# Payload.net
KiCad netlist of a schematic drawn in Altium Designer
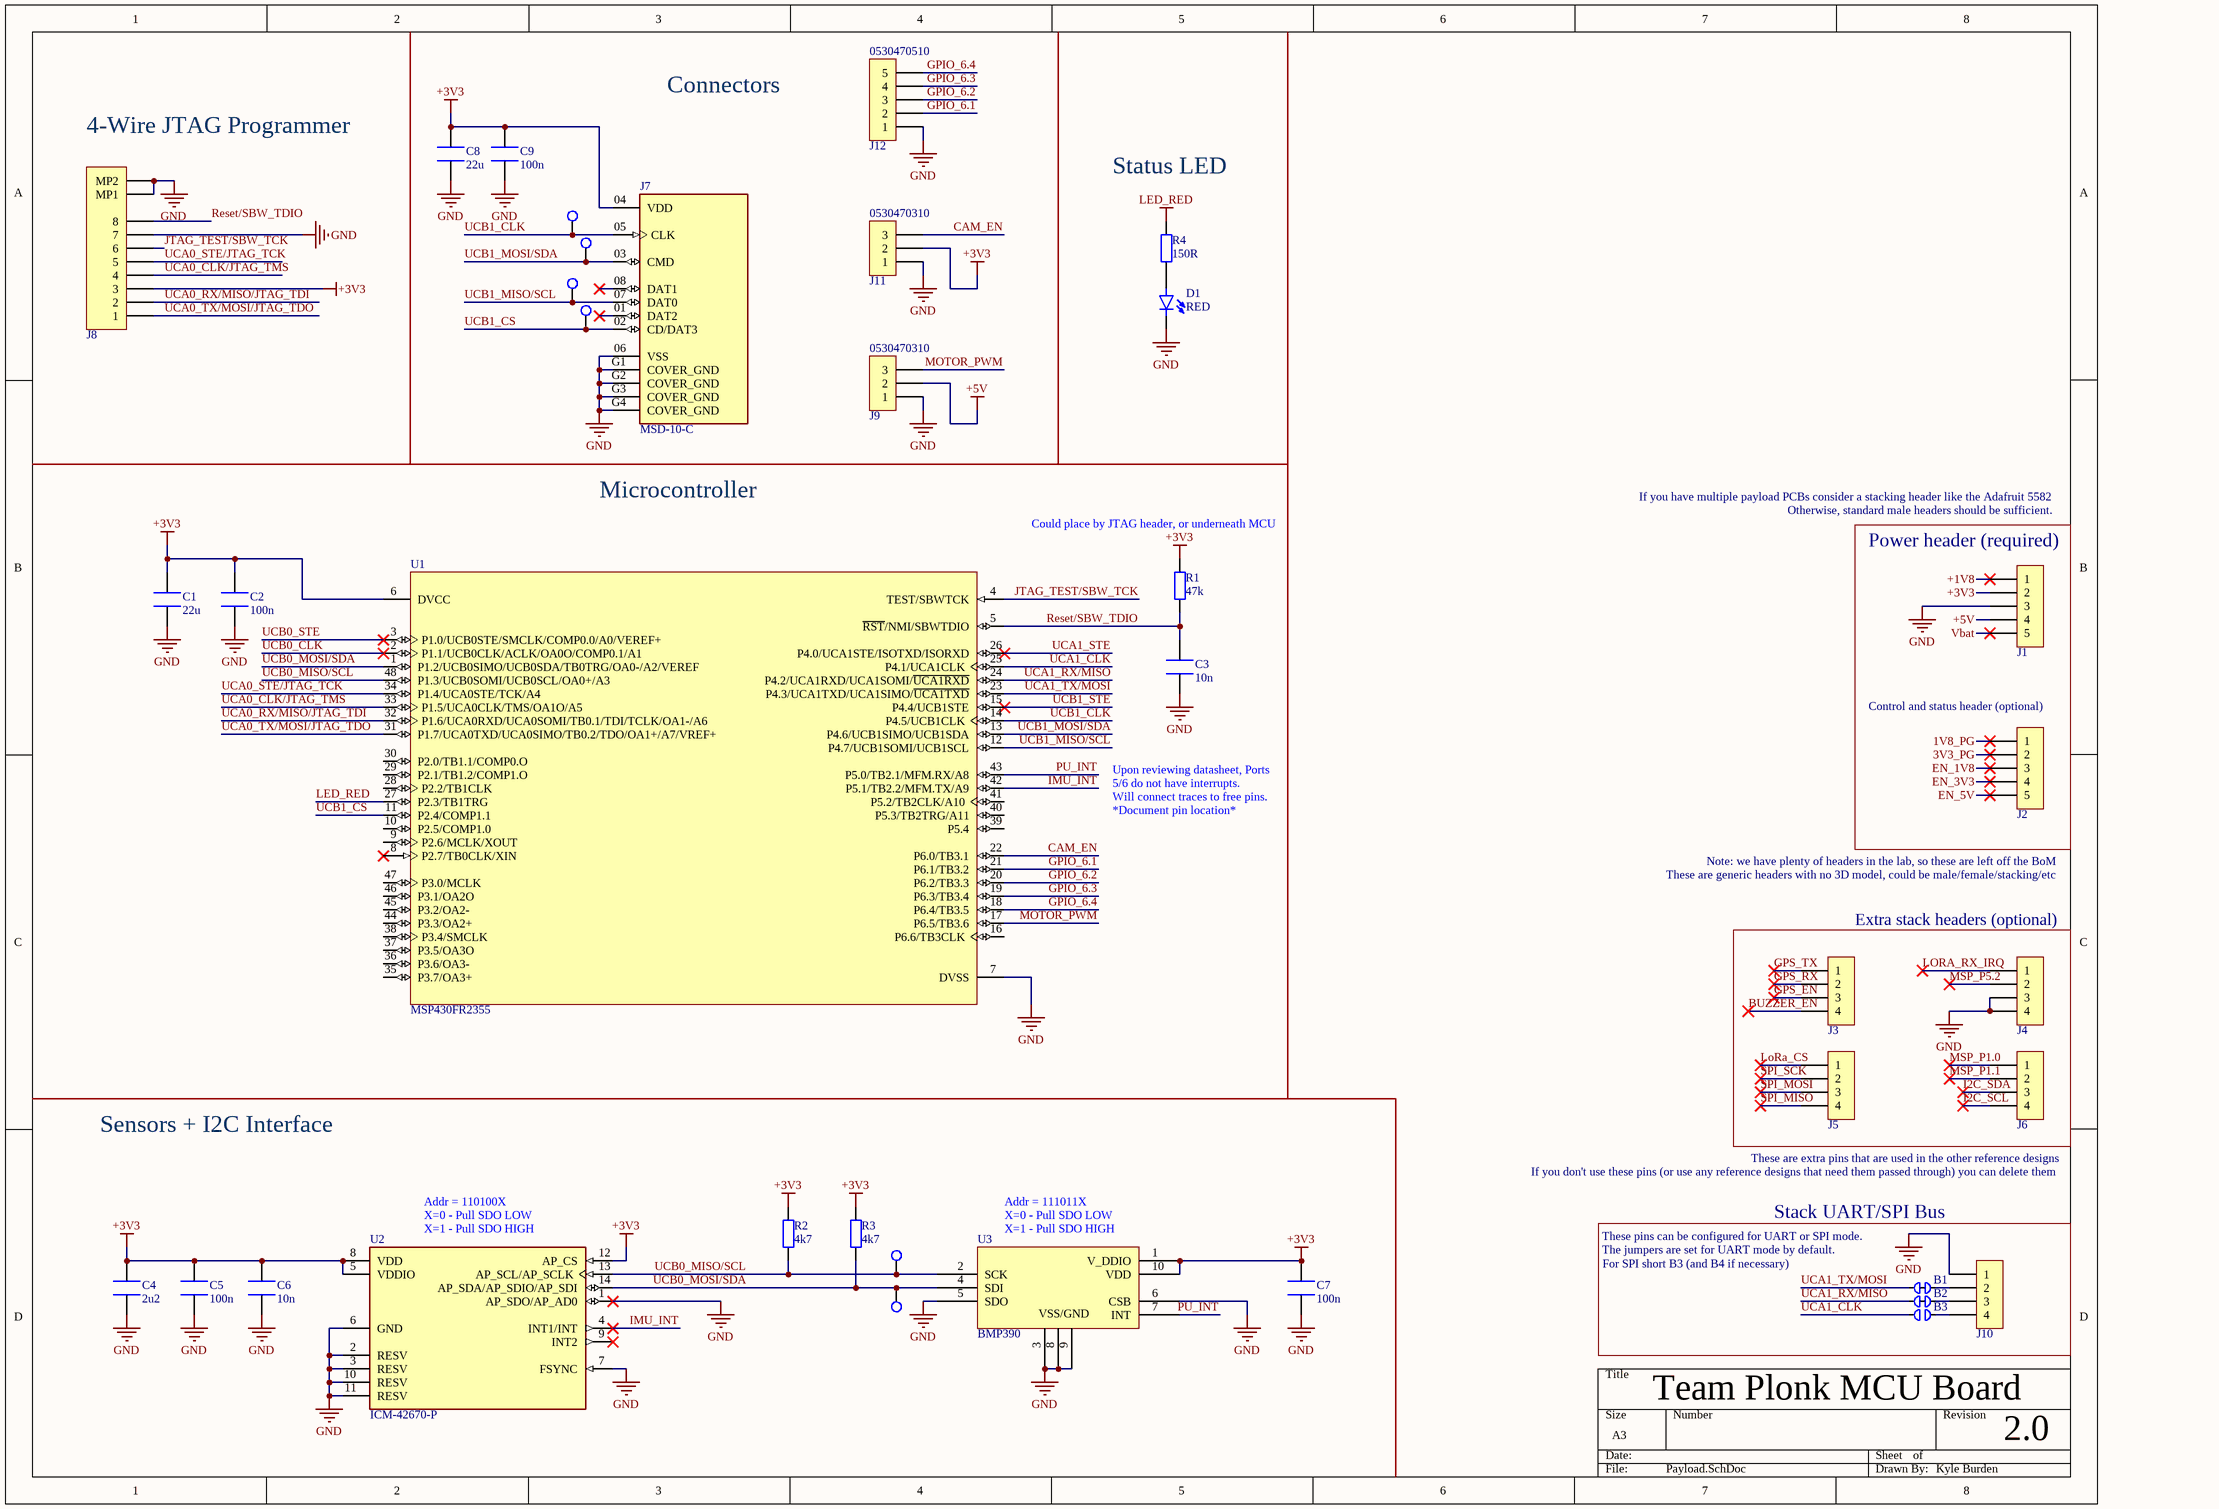
[diagram p0: Payload.SchDoc]

(export (version "E")
  (design (tool "Eeschema 10.0.6"))
  (components
    (comp (ref "B1")
      (value "Solder Jumper Normally Closed")
      (footprint "APSS Generic Components:Solder Bridge Chevron 0402 Closed")
      (libsource (lib "APSS Generic Components") (part "Solder Jumper Normally Closed"))
    )
    (comp (ref "B2")
      (value "Solder Jumper Normally Closed")
      (footprint "APSS Generic Components:Solder Bridge Chevron 0402 Closed")
      (libsource (lib "APSS Generic Components") (part "Solder Jumper Normally Closed"))
    )
    (comp (ref "B3")
      (value "Solder Jumper Normally Open")
      (footprint "APSS Generic Components:Solder Bridge Chevron 0402 Open")
      (libsource (lib "APSS Generic Components") (part "Solder Jumper Normally Open"))
    )
    (comp (ref "C1")
      (value "22u")
      (footprint "CAPACITOR_0805_2012M-70N")
      (description "Passive - Capacitor, Generic")
      (fields (field (name "TOLERANCE") "?%"))
      (libsource (lib "APSS Generic Components") (part "Generic Capacitor"))
    )
    (comp (ref "C2")
      (value "100n")
      (footprint "CAPACITOR_0805_2012M-70N")
      (description "Passive - Capacitor, Generic")
      (fields (field (name "TOLERANCE") "?%"))
      (libsource (lib "APSS Generic Components") (part "Generic Capacitor"))
    )
    (comp (ref "C3")
      (value "10n")
      (footprint "CAPACITOR_0805_2012M-70N")
      (description "Passive - Capacitor, Generic")
      (fields (field (name "TOLERANCE") "?%"))
      (libsource (lib "APSS Generic Components") (part "Generic Capacitor"))
    )
    (comp (ref "C4")
      (value "2u2")
      (footprint "CAPACITOR_0805_2012M-70N")
      (description "Passive - Capacitor, Generic")
      (fields (field (name "TOLERANCE") "?%"))
      (libsource (lib "APSS Generic Components") (part "Generic Capacitor"))
    )
    (comp (ref "C5")
      (value "100n")
      (footprint "CAPACITOR_0805_2012M-70N")
      (description "Passive - Capacitor, Generic")
      (fields (field (name "TOLERANCE") "?%"))
      (libsource (lib "APSS Generic Components") (part "Generic Capacitor"))
    )
    (comp (ref "C6")
      (value "10n")
      (footprint "CAPACITOR_0805_2012M-70N")
      (description "Passive - Capacitor, Generic")
      (fields (field (name "TOLERANCE") "?%"))
      (libsource (lib "APSS Generic Components") (part "Generic Capacitor"))
    )
    (comp (ref "C7")
      (value "100n")
      (footprint "CAPACITOR_0805_2012M-70N")
      (description "Passive - Capacitor, Generic")
      (fields (field (name "TOLERANCE") "?%"))
      (libsource (lib "APSS Generic Components") (part "Generic Capacitor"))
    )
    (comp (ref "C8")
      (value "22u")
      (footprint "CAPACITOR_0805_2012M-70N")
      (description "Passive - Capacitor, Generic")
      (fields (field (name "TOLERANCE") "?%"))
      (libsource (lib "APSS Generic Components") (part "Generic Capacitor"))
    )
    (comp (ref "C9")
      (value "100n")
      (footprint "CAPACITOR_0805_2012M-70N")
      (description "Passive - Capacitor, Generic")
      (fields (field (name "TOLERANCE") "?%"))
      (libsource (lib "APSS Generic Components") (part "Generic Capacitor"))
    )
    (comp (ref "D1")
      (value "LTST-C190 Series")
      (footprint "LED_0603_1608M_0.80mm")
      (description "Diode - LED, 0603")
      (fields (field (name "APSS STANDARD PART") "APSS Standard") (field (name "COLOUR") "RED"))
      (libsource (lib "PSAT_Library") (part "LTST-C190 Series"))
    )
    (comp (ref "J1")
      (value "Header - 2.54mm,1x5-pin")
      (footprint "HEADER_2.54MM_1x5PIN")
      (libsource (lib "APSS Generic Components") (part "Header - 2.54mm,1x5-pin"))
    )
    (comp (ref "J2")
      (value "Header - 2.54mm,1x5-pin")
      (footprint "HEADER_2.54MM_1x5PIN")
      (libsource (lib "APSS Generic Components") (part "Header - 2.54mm,1x5-pin"))
    )
    (comp (ref "J3")
      (value "Header - 2.54mm,1x4-pin")
      (footprint "HEADER_2.54MM_1x4PIN")
      (libsource (lib "APSS Generic Components") (part "Header - 2.54mm,1x4-pin"))
    )
    (comp (ref "J4")
      (value "Header - 2.54mm,1x4-pin")
      (footprint "HEADER_2.54MM_1x4PIN")
      (libsource (lib "APSS Generic Components") (part "Header - 2.54mm,1x4-pin"))
    )
    (comp (ref "J5")
      (value "Header - 2.54mm,1x4-pin")
      (footprint "HEADER_2.54MM_1x4PIN")
      (libsource (lib "APSS Generic Components") (part "Header - 2.54mm,1x4-pin"))
    )
    (comp (ref "J6")
      (value "Header - 2.54mm,1x4-pin")
      (footprint "HEADER_2.54MM_1x4PIN")
      (libsource (lib "APSS Generic Components") (part "Header - 2.54mm,1x4-pin"))
    )
    (comp (ref "J7")
      (value "MSD-10-C")
      (footprint "MSD-10-C")
      (description "SM Micro SD Card Connector")
      (libsource (lib "PSAT_Library") (part "MSD-10-C"))
    )
    (comp (ref "J8")
      (value "0532610871")
      (footprint "APSS Connectors:MOLEX_0532610871")
      (description "Connector - Picoblade 08-pin, SMT, RA")
      (fields (field (name "APSS STANDARD PART") "APSS Standard"))
      (libsource (lib "APSS Connectors") (part "0532610871"))
    )
    (comp (ref "J9")
      (value "0530470310")
      (footprint "APSS Connectors:MOLEX_0530470310")
      (description "Connector - Picoblade 03-pin, TH, STR")
      (fields (field (name "APSS STANDARD PART") "APSS Standard"))
      (libsource (lib "APSS Connectors") (part "0530470310"))
    )
    (comp (ref "J10")
      (value "HDR,2.54mm,1x4")
      (footprint "APSS Connectors:HEADER_2.54MM_1x4PIN")
      (description "Connector - 2.54mm, 1x4-pin")
      (libsource (lib "APSS Connectors") (part "HDR,2.54mm,1x4"))
    )
    (comp (ref "J11")
      (value "0530470310")
      (footprint "APSS Connectors:MOLEX_0530470310")
      (description "Connector - Picoblade 03-pin, TH, STR")
      (fields (field (name "APSS STANDARD PART") "APSS Standard"))
      (libsource (lib "APSS Connectors") (part "0530470310"))
    )
    (comp (ref "J12")
      (value "0530470510")
      (footprint "APSS Connectors:MOLEX_0530470510")
      (description "Connector - Picoblade 05-pin, TH, STR")
      (fields (field (name "APSS STANDARD PART") "APSS Standard"))
      (libsource (lib "APSS Connectors") (part "0530470510"))
    )
    (comp (ref "R1")
      (value "47k")
      (footprint "RESISTOR_0805_2012M-50N")
      (description "Passive - Resistor, Generic")
      (fields (field (name "TOLERANCE") "?%"))
      (libsource (lib "APSS Generic Components") (part "Generic Resistor"))
    )
    (comp (ref "R2")
      (value "4k7")
      (footprint "RESISTOR_0805_2012M-50N")
      (description "Passive - Resistor, Generic")
      (fields (field (name "TOLERANCE") "?%"))
      (libsource (lib "APSS Generic Components") (part "Generic Resistor"))
    )
    (comp (ref "R3")
      (value "4k7")
      (footprint "RESISTOR_0805_2012M-50N")
      (description "Passive - Resistor, Generic")
      (fields (field (name "TOLERANCE") "?%"))
      (libsource (lib "APSS Generic Components") (part "Generic Resistor"))
    )
    (comp (ref "R4")
      (value "150R")
      (footprint "Resistor_0805_2012M-50N")
      (description "0805 Surface Mount Resistor")
      (libsource (lib "PSAT_Library") (part "RES SM 0805"))
    )
    (comp (ref "TP1")
      (value "Test Point")
      (footprint "APSS Generic Components:Test Point Pad Medium")
      (libsource (lib "APSS Generic Components") (part "Test Point"))
    )
    (comp (ref "TP2")
      (value "Test Point")
      (footprint "APSS Generic Components:Test Point Pad Medium")
      (libsource (lib "APSS Generic Components") (part "Test Point"))
    )
    (comp (ref "TP3")
      (value "Test Point")
      (footprint "APSS Generic Components:Test Point Pad Medium")
      (libsource (lib "APSS Generic Components") (part "Test Point"))
    )
    (comp (ref "TP4")
      (value "Test Point")
      (footprint "APSS Generic Components:Test Point Pad Medium")
      (libsource (lib "APSS Generic Components") (part "Test Point"))
    )
    (comp (ref "TP5")
      (value "Test Point")
      (footprint "APSS Generic Components:Test Point Pad Medium")
      (libsource (lib "APSS Generic Components") (part "Test Point"))
    )
    (comp (ref "TP6")
      (value "Test Point")
      (footprint "APSS Generic Components:Test Point Pad Medium")
      (libsource (lib "APSS Generic Components") (part "Test Point"))
    )
    (comp (ref "U1")
      (value "MSP430FR2355")
      (footprint "PT0048A_N")
      (libsource (lib "PSAT_Library") (part "MSP430FR2355"))
    )
    (comp (ref "U2")
      (value "ICM-42670-P")
      (footprint "XDCR_ICM-42670-P-EXTENDED_PADS")
      (fields (field (name "APSS STANDARD PART") "APSS Standard"))
      (libsource (lib "PSAT_Library") (part "ICM-42670-P"))
    )
    (comp (ref "U3")
      (value "BMP390")
      (footprint "PSAT_Library:BMP390")
      (description "Pressure Sensor")
      (libsource (lib "PSAT_Library") (part "BMP390"))
    )
  )
  (nets
    (net (code "1") (name "+3V3") (class "Default")
      (node (ref "C1") (pin "2") (pinfunction "2_2") (pintype "passive"))
      (node (ref "C2") (pin "2") (pinfunction "2_2") (pintype "passive"))
      (node (ref "C4") (pin "2") (pinfunction "2_2") (pintype "passive"))
      (node (ref "C5") (pin "2") (pinfunction "2_2") (pintype "passive"))
      (node (ref "C6") (pin "2") (pinfunction "2_2") (pintype "passive"))
      (node (ref "C7") (pin "2") (pinfunction "2_2") (pintype "passive"))
      (node (ref "C8") (pin "2") (pinfunction "2_2") (pintype "passive"))
      (node (ref "C9") (pin "2") (pinfunction "2_2") (pintype "passive"))
      (node (ref "J1") (pin "2") (pinfunction "2_2") (pintype "passive"))
      (node (ref "J11") (pin "2") (pinfunction "2_2") (pintype "passive"))
      (node (ref "J7") (pin "04") (pinfunction "VDD_04") (pintype "power_in"))
      (node (ref "J8") (pin "3") (pinfunction "3_3") (pintype "passive"))
      (node (ref "R1") (pin "2") (pinfunction "2_2") (pintype "passive"))
      (node (ref "R2") (pin "2") (pinfunction "2_2") (pintype "passive"))
      (node (ref "R3") (pin "2") (pinfunction "2_2") (pintype "passive"))
      (node (ref "U1") (pin "6") (pinfunction "DVCC_6") (pintype "power_in"))
      (node (ref "U2") (pin "12") (pinfunction "AP_CS_12") (pintype "input"))
      (node (ref "U2") (pin "5") (pinfunction "VDDIO_5") (pintype "power_in"))
      (node (ref "U2") (pin "8") (pinfunction "VDD_8") (pintype "power_in"))
      (node (ref "U3") (pin "1") (pinfunction "V_DDIO_1") (pintype "passive"))
      (node (ref "U3") (pin "10") (pinfunction "VDD_10") (pintype "passive"))
    )
    (net (code "2") (name "+5V") (class "Default")
      (node (ref "J1") (pin "4") (pinfunction "4_4") (pintype "passive"))
      (node (ref "J9") (pin "2") (pinfunction "2_2") (pintype "passive"))
    )
    (net (code "3") (name "/+1V8") (class "Default")
      (node (ref "J1") (pin "1") (pinfunction "1_1") (pintype "passive+no_connect"))
    )
    (net (code "4") (name "/1V8_PG") (class "Default")
      (node (ref "J2") (pin "1") (pinfunction "1_1") (pintype "passive+no_connect"))
    )
    (net (code "5") (name "/3V3_PG") (class "Default")
      (node (ref "J2") (pin "2") (pinfunction "2_2") (pintype "passive+no_connect"))
    )
    (net (code "6") (name "/BUZZER_EN") (class "Default")
      (node (ref "J3") (pin "4") (pinfunction "4_4") (pintype "passive+no_connect"))
    )
    (net (code "7") (name "/CAM_EN") (class "Default")
      (node (ref "J11") (pin "3") (pinfunction "3_3") (pintype "passive"))
      (node (ref "U1") (pin "22") (pinfunction "P6.0/TB3.1_22") (pintype "bidirectional"))
    )
    (net (code "8") (name "/EN_1V8") (class "Default")
      (node (ref "J2") (pin "3") (pinfunction "3_3") (pintype "passive+no_connect"))
    )
    (net (code "9") (name "/EN_3V3") (class "Default")
      (node (ref "J2") (pin "4") (pinfunction "4_4") (pintype "passive+no_connect"))
    )
    (net (code "10") (name "/EN_5V") (class "Default")
      (node (ref "J2") (pin "5") (pinfunction "5_5") (pintype "passive+no_connect"))
    )
    (net (code "11") (name "/GPIO_6.1") (class "Default")
      (node (ref "J12") (pin "2") (pinfunction "2_2") (pintype "passive"))
      (node (ref "U1") (pin "21") (pinfunction "P6.1/TB3.2_21") (pintype "bidirectional"))
    )
    (net (code "12") (name "/GPIO_6.2") (class "Default")
      (node (ref "J12") (pin "3") (pinfunction "3_3") (pintype "passive"))
      (node (ref "U1") (pin "20") (pinfunction "P6.2/TB3.3_20") (pintype "bidirectional"))
    )
    (net (code "13") (name "/GPIO_6.3") (class "Default")
      (node (ref "J12") (pin "4") (pinfunction "4_4") (pintype "passive"))
      (node (ref "U1") (pin "19") (pinfunction "P6.3/TB3.4_19") (pintype "bidirectional"))
    )
    (net (code "14") (name "/GPIO_6.4") (class "Default")
      (node (ref "J12") (pin "5") (pinfunction "5_5") (pintype "passive"))
      (node (ref "U1") (pin "18") (pinfunction "P6.4/TB3.5_18") (pintype "bidirectional"))
    )
    (net (code "15") (name "/GPS_EN") (class "Default")
      (node (ref "J3") (pin "3") (pinfunction "3_3") (pintype "passive+no_connect"))
    )
    (net (code "16") (name "/GPS_RX") (class "Default")
      (node (ref "J3") (pin "2") (pinfunction "2_2") (pintype "passive+no_connect"))
    )
    (net (code "17") (name "/GPS_TX") (class "Default")
      (node (ref "J3") (pin "1") (pinfunction "1_1") (pintype "passive+no_connect"))
    )
    (net (code "18") (name "/I2C_SCL") (class "Default")
      (node (ref "J6") (pin "4") (pinfunction "4_4") (pintype "passive+no_connect"))
    )
    (net (code "19") (name "/I2C_SDA") (class "Default")
      (node (ref "J6") (pin "3") (pinfunction "3_3") (pintype "passive+no_connect"))
    )
    (net (code "20") (name "/IMU_INT") (class "Default")
      (node (ref "U1") (pin "42") (pinfunction "P5.1/TB2.2/MFM.TX/A9_42") (pintype "bidirectional"))
      (node (ref "U2") (pin "4") (pinfunction "INT1/INT_4") (pintype "output"))
    )
    (net (code "21") (name "/JTAG_TEST{slash}SBW_TCK") (class "Default")
      (node (ref "J8") (pin "6") (pinfunction "6_6") (pintype "passive"))
      (node (ref "U1") (pin "4") (pinfunction "TEST/SBWTCK_4") (pintype "input"))
    )
    (net (code "22") (name "/LORA_RX_IRQ") (class "Default")
      (node (ref "J4") (pin "1") (pinfunction "1_1") (pintype "passive+no_connect"))
    )
    (net (code "23") (name "/LoRa_CS") (class "Default")
      (node (ref "J5") (pin "1") (pinfunction "1_1") (pintype "passive+no_connect"))
    )
    (net (code "24") (name "/MOTOR_PWM") (class "Default")
      (node (ref "J9") (pin "3") (pinfunction "3_3") (pintype "passive"))
      (node (ref "U1") (pin "17") (pinfunction "P6.5/TB3.6_17") (pintype "bidirectional"))
    )
    (net (code "25") (name "/MSP_P1.0") (class "Default")
      (node (ref "J6") (pin "1") (pinfunction "1_1") (pintype "passive+no_connect"))
    )
    (net (code "26") (name "/MSP_P1.1") (class "Default")
      (node (ref "J6") (pin "2") (pinfunction "2_2") (pintype "passive+no_connect"))
    )
    (net (code "27") (name "/MSP_P5.2") (class "Default")
      (node (ref "J4") (pin "2") (pinfunction "2_2") (pintype "passive+no_connect"))
    )
    (net (code "28") (name "/PU_INT") (class "Default")
      (node (ref "U1") (pin "43") (pinfunction "P5.0/TB2.1/MFM.RX/A8_43") (pintype "bidirectional"))
      (node (ref "U3") (pin "7") (pinfunction "INT_7") (pintype "passive"))
    )
    (net (code "29") (name "/Reset{slash}SBW_TDIO") (class "Default")
      (node (ref "C3") (pin "2") (pinfunction "2_2") (pintype "passive"))
      (node (ref "J8") (pin "8") (pinfunction "8_8") (pintype "passive"))
      (node (ref "R1") (pin "1") (pinfunction "1_1") (pintype "passive"))
      (node (ref "U1") (pin "5") (pinfunction "~{RST}/NMI/SBWTDIO_5") (pintype "bidirectional"))
    )
    (net (code "30") (name "/SPI_MISO") (class "Default")
      (node (ref "J5") (pin "4") (pinfunction "4_4") (pintype "passive+no_connect"))
    )
    (net (code "31") (name "/SPI_MOSI") (class "Default")
      (node (ref "J5") (pin "3") (pinfunction "3_3") (pintype "passive+no_connect"))
    )
    (net (code "32") (name "/SPI_SCK") (class "Default")
      (node (ref "J5") (pin "2") (pinfunction "2_2") (pintype "passive+no_connect"))
    )
    (net (code "33") (name "/UCA0_CLK{slash}JTAG_TMS") (class "Default")
      (node (ref "J8") (pin "4") (pinfunction "4_4") (pintype "passive"))
      (node (ref "U1") (pin "33") (pinfunction "P1.5/UCA0CLK/TMS/OA1O/A5_33") (pintype "bidirectional"))
    )
    (net (code "34") (name "/UCA0_RX{slash}MISO{slash}JTAG_TDI") (class "Default")
      (node (ref "J8") (pin "2") (pinfunction "2_2") (pintype "passive"))
      (node (ref "U1") (pin "32") (pinfunction "P1.6/UCA0RXD/UCA0SOMI/TB0.1/TDI/TCLK/OA1-/A6_32") (pintype "bidirectional"))
    )
    (net (code "35") (name "/UCA0_STE{slash}JTAG_TCK") (class "Default")
      (node (ref "J8") (pin "5") (pinfunction "5_5") (pintype "passive"))
      (node (ref "U1") (pin "34") (pinfunction "P1.4/UCA0STE/TCK/A4_34") (pintype "bidirectional"))
    )
    (net (code "36") (name "/UCA0_TX{slash}MOSI{slash}JTAG_TDO") (class "Default")
      (node (ref "J8") (pin "1") (pinfunction "1_1") (pintype "passive"))
      (node (ref "U1") (pin "31") (pinfunction "P1.7/UCA0TXD/UCA0SIMO/TB0.2/TDO/OA1+/A7/VREF+_31") (pintype "bidirectional"))
    )
    (net (code "37") (name "/UCA1_CLK") (class "Default")
      (node (ref "B3") (pin "1") (pinfunction "1_1") (pintype "passive"))
      (node (ref "U1") (pin "25") (pinfunction "P4.1/UCA1CLK_25") (pintype "bidirectional"))
    )
    (net (code "38") (name "/UCA1_RX{slash}MISO") (class "Default")
      (node (ref "B2") (pin "1") (pinfunction "1_1") (pintype "passive"))
      (node (ref "U1") (pin "24") (pinfunction "P4.2/UCA1RXD/UCA1SOMI/~{UCA1RXD}_24") (pintype "bidirectional"))
    )
    (net (code "39") (name "/UCA1_STE") (class "Default")
      (node (ref "U1") (pin "26") (pinfunction "P4.0/UCA1STE/ISOTXD/ISORXD_26") (pintype "bidirectional+no_connect"))
    )
    (net (code "40") (name "/UCA1_TX{slash}MOSI") (class "Default")
      (node (ref "B1") (pin "1") (pinfunction "1_1") (pintype "passive"))
      (node (ref "U1") (pin "23") (pinfunction "P4.3/UCA1TXD/UCA1SIMO/~{UCA1TXD}_23") (pintype "bidirectional"))
    )
    (net (code "41") (name "/UCB0_CLK") (class "Default")
      (node (ref "U1") (pin "2") (pinfunction "P1.1/UCB0CLK/ACLK/OA0O/COMP0.1/A1_2") (pintype "bidirectional+no_connect"))
    )
    (net (code "42") (name "/UCB0_MISO{slash}SCL") (class "Default")
      (node (ref "R2") (pin "1") (pinfunction "1_1") (pintype "passive"))
      (node (ref "TP1") (pin "1") (pinfunction "0_1") (pintype "passive"))
      (node (ref "U1") (pin "48") (pinfunction "P1.3/UCB0SOMI/UCB0SCL/OA0+/A3_48") (pintype "bidirectional"))
      (node (ref "U2") (pin "13") (pinfunction "AP_SCL/AP_SCLK_13") (pintype "input"))
      (node (ref "U3") (pin "2") (pinfunction "SCK_2") (pintype "passive"))
    )
    (net (code "43") (name "/UCB0_MOSI{slash}SDA") (class "Default")
      (node (ref "R3") (pin "1") (pinfunction "1_1") (pintype "passive"))
      (node (ref "TP2") (pin "1") (pinfunction "0_1") (pintype "passive"))
      (node (ref "U1") (pin "1") (pinfunction "P1.2/UCB0SIMO/UCB0SDA/TB0TRG/OA0-/A2/VEREF_1") (pintype "bidirectional"))
      (node (ref "U2") (pin "14") (pinfunction "AP_SDA/AP_SDIO/AP_SDI_14") (pintype "bidirectional"))
      (node (ref "U3") (pin "4") (pinfunction "SDI_4") (pintype "passive"))
    )
    (net (code "44") (name "/UCB0_STE") (class "Default")
      (node (ref "U1") (pin "3") (pinfunction "P1.0/UCB0STE/SMCLK/COMP0.0/A0/VEREF+_3") (pintype "bidirectional+no_connect"))
    )
    (net (code "45") (name "/UCB1_CLK") (class "Default")
      (node (ref "J7") (pin "05") (pinfunction "CLK_05") (pintype "input"))
      (node (ref "TP3") (pin "1") (pinfunction "0_1") (pintype "passive"))
      (node (ref "U1") (pin "14") (pinfunction "P4.5/UCB1CLK_14") (pintype "bidirectional"))
    )
    (net (code "46") (name "/UCB1_CS") (class "Default")
      (node (ref "J7") (pin "02") (pinfunction "CD/DAT3_02") (pintype "bidirectional"))
      (node (ref "TP6") (pin "1") (pinfunction "0_1") (pintype "passive"))
      (node (ref "U1") (pin "11") (pinfunction "P2.4/COMP1.1_11") (pintype "bidirectional"))
    )
    (net (code "47") (name "/UCB1_MISO{slash}SCL") (class "Default")
      (node (ref "J7") (pin "07") (pinfunction "DAT0_07") (pintype "bidirectional"))
      (node (ref "TP5") (pin "1") (pinfunction "0_1") (pintype "passive"))
      (node (ref "U1") (pin "12") (pinfunction "P4.7/UCB1SOMI/UCB1SCL_12") (pintype "bidirectional"))
    )
    (net (code "48") (name "/UCB1_MOSI{slash}SDA") (class "Default")
      (node (ref "J7") (pin "03") (pinfunction "CMD_03") (pintype "bidirectional"))
      (node (ref "TP4") (pin "1") (pinfunction "0_1") (pintype "passive"))
      (node (ref "U1") (pin "13") (pinfunction "P4.6/UCB1SIMO/UCB1SDA_13") (pintype "bidirectional"))
    )
    (net (code "49") (name "/UCB1_STE") (class "Default")
      (node (ref "U1") (pin "15") (pinfunction "P4.4/UCB1STE_15") (pintype "bidirectional+no_connect"))
    )
    (net (code "50") (name "/Vbat") (class "Default")
      (node (ref "J1") (pin "5") (pinfunction "5_5") (pintype "passive+no_connect"))
    )
    (net (code "51") (name "GND") (class "Default")
      (node (ref "C1") (pin "1") (pinfunction "1_1") (pintype "passive"))
      (node (ref "C2") (pin "1") (pinfunction "1_1") (pintype "passive"))
      (node (ref "C3") (pin "1") (pinfunction "1_1") (pintype "passive"))
      (node (ref "C4") (pin "1") (pinfunction "1_1") (pintype "passive"))
      (node (ref "C5") (pin "1") (pinfunction "1_1") (pintype "passive"))
      (node (ref "C6") (pin "1") (pinfunction "1_1") (pintype "passive"))
      (node (ref "C7") (pin "1") (pinfunction "1_1") (pintype "passive"))
      (node (ref "C8") (pin "1") (pinfunction "1_1") (pintype "passive"))
      (node (ref "C9") (pin "1") (pinfunction "1_1") (pintype "passive"))
      (node (ref "D1") (pin "C") (pinfunction "C_C") (pintype "passive"))
      (node (ref "J1") (pin "3") (pinfunction "3_3") (pintype "passive"))
      (node (ref "J10") (pin "1") (pinfunction "1_1") (pintype "passive"))
      (node (ref "J11") (pin "1") (pinfunction "1_1") (pintype "passive"))
      (node (ref "J12") (pin "1") (pinfunction "1_1") (pintype "passive"))
      (node (ref "J4") (pin "3") (pinfunction "3_3") (pintype "passive"))
      (node (ref "J4") (pin "4") (pinfunction "4_4") (pintype "passive"))
      (node (ref "J7") (pin "06") (pinfunction "VSS_06") (pintype "power_in"))
      (node (ref "J7") (pin "G1") (pinfunction "COVER_GND_G1") (pintype "power_in"))
      (node (ref "J7") (pin "G2") (pinfunction "COVER_GND_G2") (pintype "power_in"))
      (node (ref "J7") (pin "G3") (pinfunction "COVER_GND_G3") (pintype "power_in"))
      (node (ref "J7") (pin "G4") (pinfunction "COVER_GND_G4") (pintype "power_in"))
      (node (ref "J8") (pin "7") (pinfunction "7_7") (pintype "passive"))
      (node (ref "J8") (pin "MP1") (pinfunction "MP1_MP1") (pintype "passive"))
      (node (ref "J8") (pin "MP2") (pinfunction "MP2_MP2") (pintype "passive"))
      (node (ref "J9") (pin "1") (pinfunction "1_1") (pintype "passive"))
      (node (ref "U1") (pin "7") (pinfunction "DVSS_7") (pintype "power_in"))
      (node (ref "U2") (pin "1") (pinfunction "AP_SDO/AP_AD0_1") (pintype "bidirectional"))
      (node (ref "U2") (pin "10") (pinfunction "RESV_10") (pintype "passive"))
      (node (ref "U2") (pin "11") (pinfunction "RESV_11") (pintype "passive"))
      (node (ref "U2") (pin "2") (pinfunction "RESV_2") (pintype "passive"))
      (node (ref "U2") (pin "3") (pinfunction "RESV_3") (pintype "passive"))
      (node (ref "U2") (pin "6") (pinfunction "GND_6") (pintype "power_in"))
      (node (ref "U2") (pin "7") (pinfunction "FSYNC_7") (pintype "input"))
      (node (ref "U3") (pin "3") (pinfunction "V_SS/GND_3") (pintype "passive"))
      (node (ref "U3") (pin "5") (pinfunction "SDO_5") (pintype "passive"))
      (node (ref "U3") (pin "6") (pinfunction "CSB_6") (pintype "passive"))
      (node (ref "U3") (pin "8") (pinfunction "V_SS/GND_8") (pintype "passive"))
      (node (ref "U3") (pin "9") (pinfunction "V_SS/GND_9") (pintype "passive"))
    )
    (net (code "52") (name "LED_RED") (class "Default")
      (node (ref "R4") (pin "2") (pinfunction "2_2") (pintype "passive"))
      (node (ref "U1") (pin "27") (pinfunction "P2.3/TB1TRG_27") (pintype "bidirectional"))
    )
    (net (code "53") (name "Net-(B1-Pad2)") (class "Default")
      (node (ref "B1") (pin "2") (pinfunction "2_2") (pintype "passive"))
      (node (ref "J10") (pin "2") (pinfunction "2_2") (pintype "passive"))
    )
    (net (code "54") (name "Net-(B2-Pad2)") (class "Default")
      (node (ref "B2") (pin "2") (pinfunction "2_2") (pintype "passive"))
      (node (ref "J10") (pin "3") (pinfunction "3_3") (pintype "passive"))
    )
    (net (code "55") (name "Net-(B3-Pad2)") (class "Default")
      (node (ref "B3") (pin "2") (pinfunction "2_2") (pintype "passive"))
      (node (ref "J10") (pin "4") (pinfunction "4_4") (pintype "passive"))
    )
    (net (code "56") (name "Net-(D1-PadA)") (class "Default")
      (node (ref "D1") (pin "A") (pinfunction "A_A") (pintype "passive"))
      (node (ref "R4") (pin "1") (pinfunction "1_1") (pintype "passive"))
    )
    (net (code "57") (name "unconnected-(J7-DAT1-Pad08)") (class "Default")
      (node (ref "J7") (pin "08") (pinfunction "DAT1_08") (pintype "bidirectional+no_connect"))
    )
    (net (code "58") (name "unconnected-(J7-DAT2-Pad01)") (class "Default")
      (node (ref "J7") (pin "01") (pinfunction "DAT2_01") (pintype "bidirectional+no_connect"))
    )
    (net (code "59") (name "unconnected-(U1-P2.0{slash}TB1.1{slash}COMP0.O-Pad30)") (class "Default")
      (node (ref "U1") (pin "30") (pinfunction "P2.0/TB1.1/COMP0.O_30") (pintype "bidirectional"))
    )
    (net (code "60") (name "unconnected-(U1-P2.1{slash}TB1.2{slash}COMP1.O-Pad29)") (class "Default")
      (node (ref "U1") (pin "29") (pinfunction "P2.1/TB1.2/COMP1.O_29") (pintype "bidirectional"))
    )
    (net (code "61") (name "unconnected-(U1-P2.2{slash}TB1CLK-Pad28)") (class "Default")
      (node (ref "U1") (pin "28") (pinfunction "P2.2/TB1CLK_28") (pintype "bidirectional"))
    )
    (net (code "62") (name "unconnected-(U1-P2.5{slash}COMP1.0-Pad10)") (class "Default")
      (node (ref "U1") (pin "10") (pinfunction "P2.5/COMP1.0_10") (pintype "bidirectional"))
    )
    (net (code "63") (name "unconnected-(U1-P2.6{slash}MCLK{slash}XOUT-Pad9)") (class "Default")
      (node (ref "U1") (pin "9") (pinfunction "P2.6/MCLK/XOUT_9") (pintype "bidirectional"))
    )
    (net (code "64") (name "unconnected-(U1-P2.7{slash}TB0CLK{slash}XIN-Pad8)") (class "Default")
      (node (ref "U1") (pin "8") (pinfunction "P2.7/TB0CLK/XIN_8") (pintype "input+no_connect"))
    )
    (net (code "65") (name "unconnected-(U1-P3.0{slash}MCLK-Pad47)") (class "Default")
      (node (ref "U1") (pin "47") (pinfunction "P3.0/MCLK_47") (pintype "bidirectional"))
    )
    (net (code "66") (name "unconnected-(U1-P3.1{slash}OA2O-Pad46)") (class "Default")
      (node (ref "U1") (pin "46") (pinfunction "P3.1/OA2O_46") (pintype "bidirectional"))
    )
    (net (code "67") (name "unconnected-(U1-P3.2{slash}OA2--Pad45)") (class "Default")
      (node (ref "U1") (pin "45") (pinfunction "P3.2/OA2-_45") (pintype "bidirectional"))
    )
    (net (code "68") (name "unconnected-(U1-P3.3{slash}OA2+-Pad44)") (class "Default")
      (node (ref "U1") (pin "44") (pinfunction "P3.3/OA2+_44") (pintype "bidirectional"))
    )
    (net (code "69") (name "unconnected-(U1-P3.4{slash}SMCLK-Pad38)") (class "Default")
      (node (ref "U1") (pin "38") (pinfunction "P3.4/SMCLK_38") (pintype "bidirectional"))
    )
    (net (code "70") (name "unconnected-(U1-P3.5{slash}OA3O-Pad37)") (class "Default")
      (node (ref "U1") (pin "37") (pinfunction "P3.5/OA3O_37") (pintype "bidirectional"))
    )
    (net (code "71") (name "unconnected-(U1-P3.6{slash}OA3--Pad36)") (class "Default")
      (node (ref "U1") (pin "36") (pinfunction "P3.6/OA3-_36") (pintype "bidirectional"))
    )
    (net (code "72") (name "unconnected-(U1-P3.7{slash}OA3+-Pad35)") (class "Default")
      (node (ref "U1") (pin "35") (pinfunction "P3.7/OA3+_35") (pintype "bidirectional"))
    )
    (net (code "73") (name "unconnected-(U1-P5.2{slash}TB2CLK{slash}A10-Pad41)") (class "Default")
      (node (ref "U1") (pin "41") (pinfunction "P5.2/TB2CLK/A10_41") (pintype "bidirectional"))
    )
    (net (code "74") (name "unconnected-(U1-P5.3{slash}TB2TRG{slash}A11-Pad40)") (class "Default")
      (node (ref "U1") (pin "40") (pinfunction "P5.3/TB2TRG/A11_40") (pintype "bidirectional"))
    )
    (net (code "75") (name "unconnected-(U1-P5.4-Pad39)") (class "Default")
      (node (ref "U1") (pin "39") (pinfunction "P5.4_39") (pintype "bidirectional"))
    )
    (net (code "76") (name "unconnected-(U1-P6.6{slash}TB3CLK-Pad16)") (class "Default")
      (node (ref "U1") (pin "16") (pinfunction "P6.6/TB3CLK_16") (pintype "bidirectional"))
    )
    (net (code "77") (name "unconnected-(U2-INT2-Pad9)") (class "Default")
      (node (ref "U2") (pin "9") (pinfunction "INT2_9") (pintype "output+no_connect"))
    )
  )
)
